# LMR14050_mod.net
KiCad netlist of a schematic drawn in Altium Designer
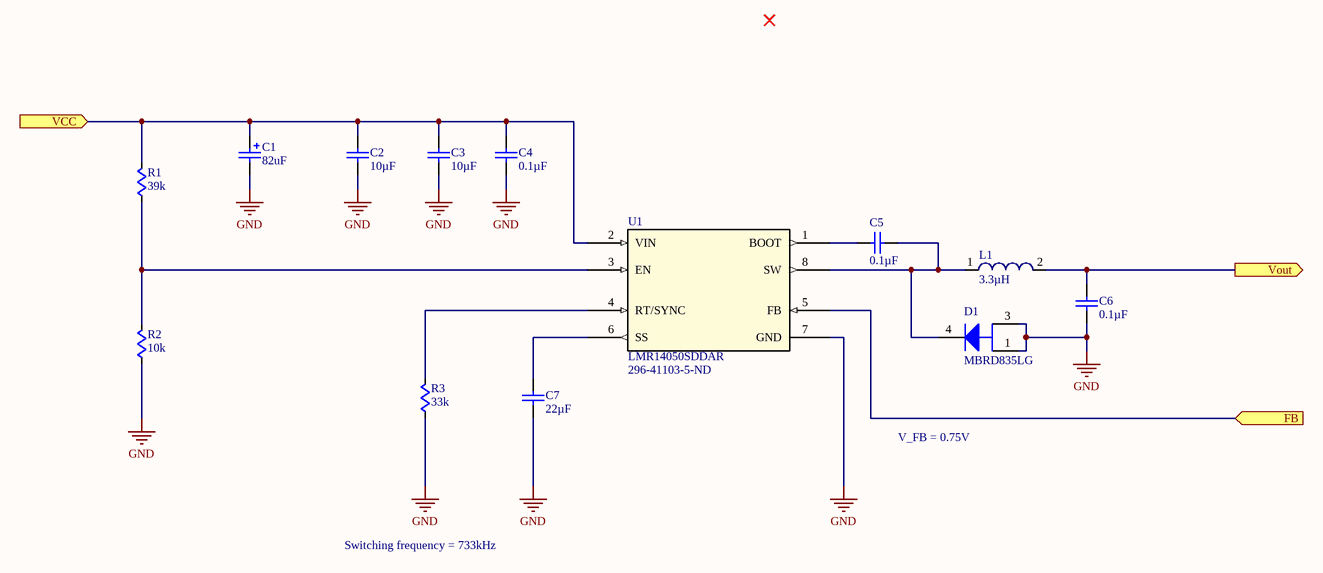
[diagram p0: LMR14050_mod.SchDoc]

(export (version "E")
  (design (tool "Eeschema 10.0.6"))
  (components
    (comp (ref "C1")
      (value "82uF")
      (footprint "CAP_EEFK_D8")
      (description "Polarized Capacitor (Surface Mount)")
      (fields (field (name "MANUFACTURER_PART_NUMBER") "EEEFK1V680XP"))
      (libsource (lib "AEVC-lib") (part "EEEFK1V680XP"))
    )
    (comp (ref "C2")
      (value "10µF")
      (footprint "C0805")
      (description "capacitor")
      (fields (field (name "Comment") "Cap"))
      (libsource (lib "ChipComponents") (part "Cap"))
    )
    (comp (ref "C3")
      (value "10µF")
      (footprint "C0805")
      (description "capacitor")
      (fields (field (name "Comment") "Cap"))
      (libsource (lib "ChipComponents") (part "Cap"))
    )
    (comp (ref "C4")
      (value "0.1µF")
      (footprint "C0805")
      (description "capacitor")
      (fields (field (name "Comment") "Cap"))
      (libsource (lib "ChipComponents") (part "Cap"))
    )
    (comp (ref "C5")
      (value "0.1µF")
      (footprint "C0805")
      (description "capacitor")
      (fields (field (name "Comment") "Cap"))
      (libsource (lib "ChipComponents") (part "Cap"))
    )
    (comp (ref "C6")
      (value "0.1µF")
      (footprint "C0805")
      (description "capacitor")
      (fields (field (name "Comment") "Cap"))
      (libsource (lib "ChipComponents") (part "Cap"))
    )
    (comp (ref "C7")
      (value "22µF")
      (footprint "C0805")
      (description "capacitor")
      (fields (field (name "Comment") "Cap"))
      (libsource (lib "ChipComponents") (part "Cap"))
    )
    (comp (ref "D1")
      (value "MBRD835LG")
      (footprint "ONSC-DPAK-3-369C-01_V")
      (description "SWITCHMODE(TM) Power Rectifier, 3-Pin DPAK, Pb-Free, Tube")
      (fields (field (name "MANUFACTURER") "On Semiconductor"))
      (libsource (lib "Altium Content Vault") (part "ONSC-D-A1A3K4-3_A"))
    )
    (comp (ref "L1")
      (value "3.3µH")
      (footprint "IHLP-2525C7")
      (description "Inductor")
      (fields (field (name "Comment") "Ind"))
      (libsource (lib "AEVC-bodyBoard") (part "Ind"))
    )
    (comp (ref "R1")
      (value "39k")
      (footprint "R0805")
      (description "resistor")
      (fields (field (name "Comment") "Res"))
      (libsource (lib "ChipComponents") (part "Res"))
    )
    (comp (ref "R2")
      (value "10k")
      (footprint "R0805")
      (description "resistor")
      (fields (field (name "Comment") "Res"))
      (libsource (lib "ChipComponents") (part "Res"))
    )
    (comp (ref "R3")
      (value "33k")
      (footprint "R0805")
      (description "resistor")
      (fields (field (name "Comment") "Res"))
      (libsource (lib "ChipComponents") (part "Res"))
    )
    (comp (ref "U1")
      (value "LMR14050SDDAR")
      (footprint "DDA8")
      (description "dc-dc converter")
      (fields (field (name "SUPPLIER PART NUMBER 1") "296-41103-5-ND"))
      (libsource (lib "AEVC-lib") (part "LMR14050SDDAR"))
    )
  )
  (nets
    (net (code "1") (name "/FB") (class "Default")
      (node (ref "U1") (pin "5") (pinfunction "FB_5") (pintype "input"))
    )
    (net (code "2") (name "/VCC") (class "Default")
      (node (ref "C1") (pin "1") (pinfunction "1_1") (pintype "passive"))
      (node (ref "C2") (pin "2") (pinfunction "2_2") (pintype "passive"))
      (node (ref "C3") (pin "2") (pinfunction "2_2") (pintype "passive"))
      (node (ref "C4") (pin "2") (pinfunction "2_2") (pintype "passive"))
      (node (ref "R1") (pin "2") (pinfunction "2_2") (pintype "passive"))
      (node (ref "U1") (pin "2") (pinfunction "VIN_2") (pintype "input"))
    )
    (net (code "3") (name "/Vout") (class "Default")
      (node (ref "C6") (pin "2") (pinfunction "2_2") (pintype "passive"))
      (node (ref "L1") (pin "2") (pinfunction "2_2") (pintype "passive"))
    )
    (net (code "4") (name "GND") (class "Default")
      (node (ref "C1") (pin "2") (pinfunction "2_2") (pintype "passive"))
      (node (ref "C2") (pin "1") (pinfunction "1_1") (pintype "passive"))
      (node (ref "C3") (pin "1") (pinfunction "1_1") (pintype "passive"))
      (node (ref "C4") (pin "1") (pinfunction "1_1") (pintype "passive"))
      (node (ref "C6") (pin "1") (pinfunction "1_1") (pintype "passive"))
      (node (ref "C7") (pin "1") (pinfunction "1_1") (pintype "passive"))
      (node (ref "D1") (pin "1") (pinfunction "A_1") (pintype "passive"))
      (node (ref "D1") (pin "3") (pinfunction "A_3") (pintype "passive"))
      (node (ref "R2") (pin "1") (pinfunction "1_1") (pintype "passive"))
      (node (ref "R3") (pin "1") (pinfunction "1_1") (pintype "passive"))
      (node (ref "U1") (pin "7") (pinfunction "GND_7") (pintype "power_in"))
    )
    (net (code "5") (name "Net-(D1-K)") (class "Default")
      (node (ref "C5") (pin "1") (pinfunction "1_1") (pintype "passive"))
      (node (ref "D1") (pin "4") (pinfunction "K_4") (pintype "passive"))
      (node (ref "L1") (pin "1") (pinfunction "1_1") (pintype "passive"))
      (node (ref "U1") (pin "8") (pinfunction "SW_8") (pintype "output"))
    )
    (net (code "6") (name "Net-(U1-BOOT)") (class "Default")
      (node (ref "C5") (pin "2") (pinfunction "2_2") (pintype "passive"))
      (node (ref "U1") (pin "1") (pinfunction "BOOT_1") (pintype "output"))
    )
    (net (code "7") (name "Net-(U1-EN)") (class "Default")
      (node (ref "R1") (pin "1") (pinfunction "1_1") (pintype "passive"))
      (node (ref "R2") (pin "2") (pinfunction "2_2") (pintype "passive"))
      (node (ref "U1") (pin "3") (pinfunction "EN_3") (pintype "input"))
    )
    (net (code "8") (name "Net-(U1-RT{slash}SYNC)") (class "Default")
      (node (ref "R3") (pin "2") (pinfunction "2_2") (pintype "passive"))
      (node (ref "U1") (pin "4") (pinfunction "RT/SYNC_4") (pintype "input"))
    )
    (net (code "9") (name "Net-(U1-SS)") (class "Default")
      (node (ref "C7") (pin "2") (pinfunction "2_2") (pintype "passive"))
      (node (ref "U1") (pin "6") (pinfunction "SS_6") (pintype "output"))
    )
  )
)
